# Sheet2.net
KiCad netlist of a schematic drawn in Altium Designer
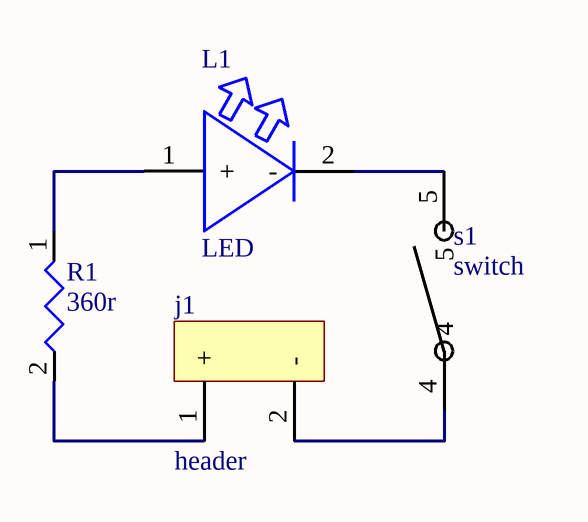
[diagram p0: Sheet2.SchDoc]

(export (version "E")
  (design (tool "Eeschema 10.0.6"))
  (components
    (comp (ref "j1")
      (value "header")
      (footprint "PcbLib1:HDR1X2")
      (description "Board Connector, 2 Contact(s), 1 Row(s), Male, Straight, Solder Terminal")
      (fields (field (name "MANUFACTURER") "Molex") (field (name "MANUFACTURER PART NUMBER") "0022292021"))
      (libsource (lib "Schlib1") (part "0022292021"))
    )
    (comp (ref "L1")
      (value "LED")
      (footprint "LED")
      (description "Single Color LED, Cool White, 2.6mm")
      (fields
        (field (name "MANUFACTURER") "Cree")
        (field (name "MANUFACTURER PART NUMBER") "JB3030AWT-P-H65EA0000-N0000001")
      )
      (libsource (lib "Schlib1") (part "732-12017-2-ND"))
    )
    (comp (ref "R1")
      (value "360r")
      (footprint "R0805")
      (fields
        (field (name "MANUFACTURER") "Vishay")
        (field (name "MANUFACTURER PART NUMBER") "CRCW0805360RFKEA")
        (field (name "TOLERANCE") "1%")
      )
      (libsource (lib "Schlib1") (part "CRCW0805360RFKEA"))
    )
    (comp (ref "s1")
      (value "switch")
      (footprint "Push button")
      (fields
        (field (name "MANUFACTURER") "NKK Switches")
        (field (name "MANUFACTURER PART NUMBER") "G3T12AB")
      )
      (libsource (lib "Schlib1") (part "G3T12AB"))
    )
  )
  (nets
    (net (code "1") (name "Net-(L1-+)") (class "Default")
      (node (ref "L1") (pin "1") (pinfunction "+_1") (pintype "passive"))
      (node (ref "R1") (pin "1") (pinfunction "1_1") (pintype "passive"))
    )
    (net (code "2") (name "Net-(L1--)") (class "Default")
      (node (ref "L1") (pin "2") (pinfunction "-_2") (pintype "passive"))
      (node (ref "s1") (pin "5") (pinfunction "5_5") (pintype "passive"))
    )
    (net (code "3") (name "Net-(j1-+)") (class "Default")
      (node (ref "R1") (pin "2") (pinfunction "2_2") (pintype "passive"))
      (node (ref "j1") (pin "1") (pinfunction "+_1") (pintype "passive"))
    )
    (net (code "4") (name "Net-(j1--)") (class "Default")
      (node (ref "j1") (pin "2") (pinfunction "-_2") (pintype "passive"))
      (node (ref "s1") (pin "4") (pinfunction "4_4") (pintype "passive"))
    )
  )
)
